# Connectors.net
KiCad netlist of a schematic drawn in Altium Designer
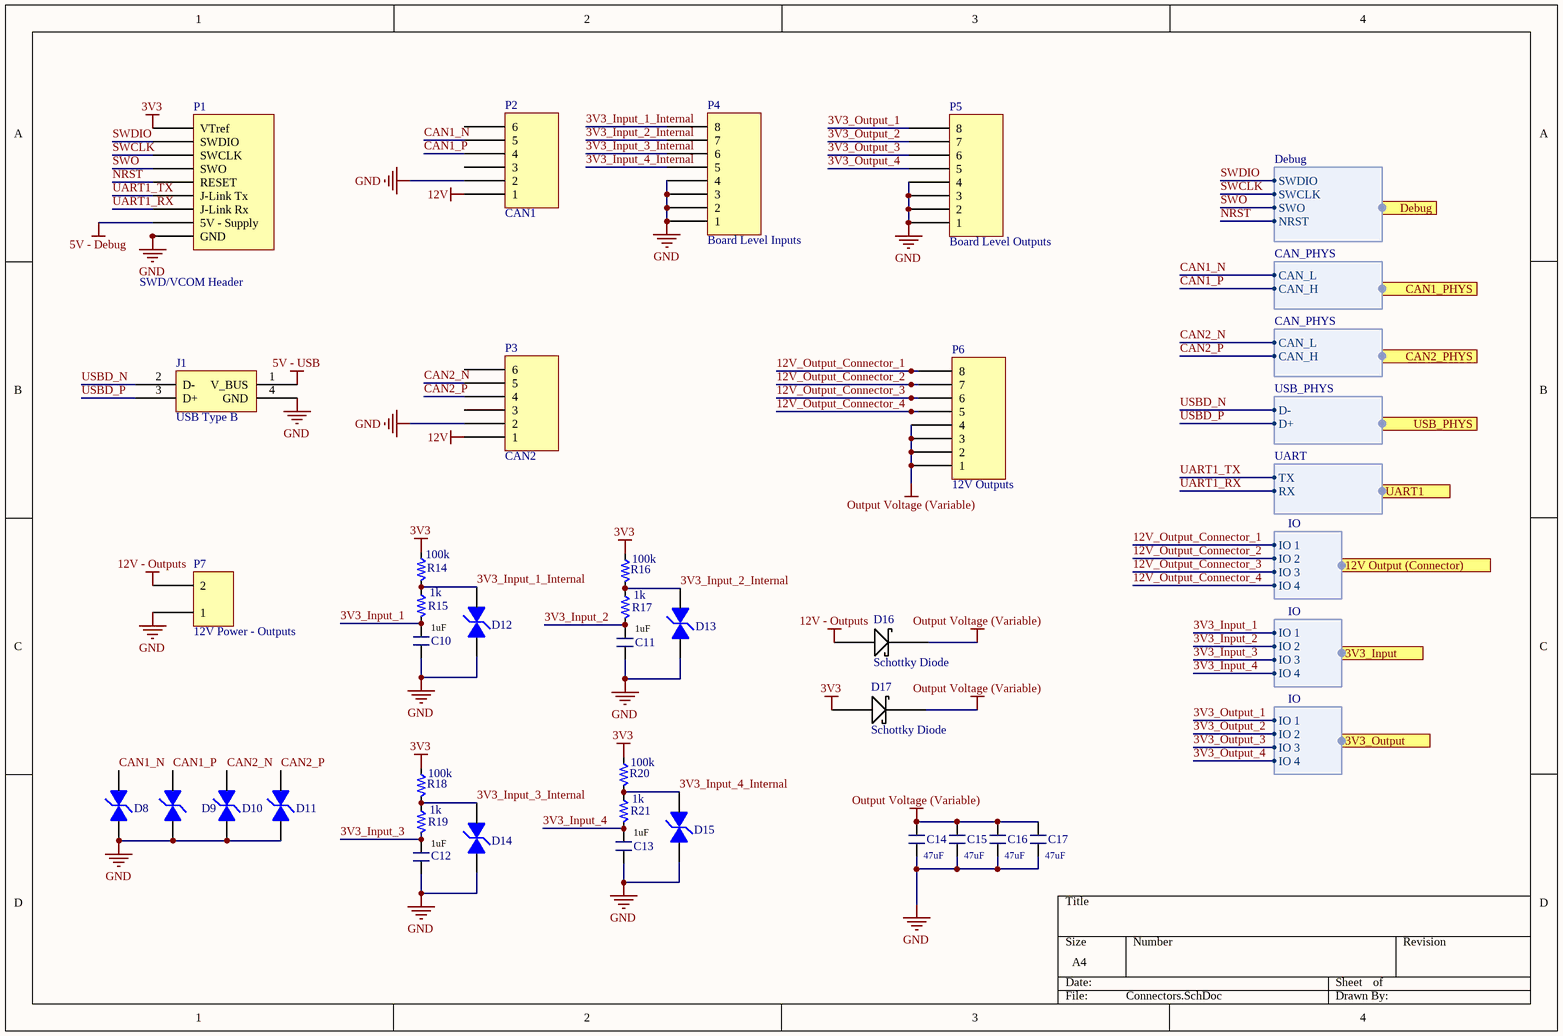
[diagram p0: Connectors.SchDoc]

(export (version "E")
  (design (tool "Eeschema 10.0.6"))
  (components
    (comp (ref "C10")
      (value "SCH_GENERIC_CAPACITOR_0603")
      (footprint "PCB_GENERIC_SMD_0603")
      (description "Generic SMD capacitor 0603")
      (fields (field (name "TOLERANCE") "*%") (field (name "CAPACITANCE") "1uF"))
      (libsource (lib "Generic 0603 Capacitor") (part "SCH_GENERIC_CAPACITOR_0603"))
    )
    (comp (ref "C11")
      (value "SCH_GENERIC_CAPACITOR_0603")
      (footprint "PCB_GENERIC_SMD_0603")
      (description "Generic SMD capacitor 0603")
      (fields (field (name "TOLERANCE") "*%") (field (name "CAPACITANCE") "1uF"))
      (libsource (lib "Generic 0603 Capacitor") (part "SCH_GENERIC_CAPACITOR_0603"))
    )
    (comp (ref "C12")
      (value "SCH_GENERIC_CAPACITOR_0603")
      (footprint "PCB_GENERIC_SMD_0603")
      (description "Generic SMD capacitor 0603")
      (fields (field (name "TOLERANCE") "*%") (field (name "CAPACITANCE") "1uF"))
      (libsource (lib "Generic 0603 Capacitor") (part "SCH_GENERIC_CAPACITOR_0603"))
    )
    (comp (ref "C13")
      (value "SCH_GENERIC_CAPACITOR_0603")
      (footprint "PCB_GENERIC_SMD_0603")
      (description "Generic SMD capacitor 0603")
      (fields (field (name "TOLERANCE") "*%") (field (name "CAPACITANCE") "1uF"))
      (libsource (lib "Generic 0603 Capacitor") (part "SCH_GENERIC_CAPACITOR_0603"))
    )
    (comp (ref "C14")
      (value "SCH_GENERIC_CAPACITOR_1210")
      (footprint "PCB_GENERIC_CAPACITOR_1210")
      (description "Generic SMD capacitor 1210")
      (fields (field (name "CAPACITANCE") "47uF"))
      (libsource (lib "Generic 1210 Capacitor") (part "SCH_GENERIC_CAPACITOR_1210"))
    )
    (comp (ref "C15")
      (value "SCH_GENERIC_CAPACITOR_1210")
      (footprint "PCB_GENERIC_CAPACITOR_1210")
      (description "Generic SMD capacitor 1210")
      (fields (field (name "CAPACITANCE") "47uF"))
      (libsource (lib "Generic 1210 Capacitor") (part "SCH_GENERIC_CAPACITOR_1210"))
    )
    (comp (ref "C16")
      (value "SCH_GENERIC_CAPACITOR_1210")
      (footprint "PCB_GENERIC_CAPACITOR_1210")
      (description "Generic SMD capacitor 1210")
      (fields (field (name "CAPACITANCE") "47uF"))
      (libsource (lib "Generic 1210 Capacitor") (part "SCH_GENERIC_CAPACITOR_1210"))
    )
    (comp (ref "C17")
      (value "SCH_GENERIC_CAPACITOR_1210")
      (footprint "PCB_GENERIC_CAPACITOR_1210")
      (description "Generic SMD capacitor 1210")
      (fields (field (name "CAPACITANCE") "47uF"))
      (libsource (lib "Generic 1210 Capacitor") (part "SCH_GENERIC_CAPACITOR_1210"))
    )
    (comp (ref "D8")
      (value "TVS Diode")
      (footprint "TVS Diode")
      (fields (field (name "MANUFACTURER") "Bourns"))
      (libsource (lib "TVS Diode") (part "TVS Diode"))
    )
    (comp (ref "D9")
      (value "TVS Diode")
      (footprint "TVS Diode")
      (fields (field (name "MANUFACTURER") "Bourns"))
      (libsource (lib "TVS Diode") (part "TVS Diode"))
    )
    (comp (ref "D10")
      (value "TVS Diode")
      (footprint "TVS Diode")
      (fields (field (name "MANUFACTURER") "Bourns"))
      (libsource (lib "TVS Diode") (part "TVS Diode"))
    )
    (comp (ref "D11")
      (value "TVS Diode")
      (footprint "TVS Diode")
      (fields (field (name "MANUFACTURER") "Bourns"))
      (libsource (lib "TVS Diode") (part "TVS Diode"))
    )
    (comp (ref "D12")
      (value "TVS Diode")
      (footprint "TVS Diode")
      (fields (field (name "MANUFACTURER") "Bourns"))
      (libsource (lib "TVS Diode") (part "TVS Diode"))
    )
    (comp (ref "D13")
      (value "TVS Diode")
      (footprint "TVS Diode")
      (fields (field (name "MANUFACTURER") "Bourns"))
      (libsource (lib "TVS Diode") (part "TVS Diode"))
    )
    (comp (ref "D14")
      (value "TVS Diode")
      (footprint "TVS Diode")
      (fields (field (name "MANUFACTURER") "Bourns"))
      (libsource (lib "TVS Diode") (part "TVS Diode"))
    )
    (comp (ref "D15")
      (value "TVS Diode")
      (footprint "TVS Diode")
      (fields (field (name "MANUFACTURER") "Bourns"))
      (libsource (lib "TVS Diode") (part "TVS Diode"))
    )
    (comp (ref "D16")
      (value "Schottky Diode")
      (footprint "ON Semi Schottky Diode - MBRM110LT1G")
      (libsource (lib "ON Semi Schottky Diode") (part "ON Semi Schottky Diode - MBRM110LT1G"))
    )
    (comp (ref "D17")
      (value "Schottky Diode")
      (footprint "ON Semi Schottky Diode - MBRM110LT1G")
      (libsource (lib "ON Semi Schottky Diode") (part "ON Semi Schottky Diode - MBRM110LT1G"))
    )
    (comp (ref "J1")
      (value "USB Type B")
      (footprint "0670688000")
      (libsource (lib "USB Type B Right Angle") (part "0670688000"))
    )
    (comp (ref "P1")
      (value "SWD/VCOM Header")
      (footprint "Samtec TST-110-01-G-D")
      (libsource (lib "SWD+VCOM Header - J-Link") (part "SWD/VCOM Header"))
    )
    (comp (ref "P2")
      (value "CAN1")
      (footprint "Molex Microfit 3.0 3x2:PCB_MLX_MICROFIT_3X2")
      (libsource (lib "Molex Microfit 3.0 3x2") (part "SCH_MLX_MICROFIT_3X2"))
    )
    (comp (ref "P3")
      (value "CAN2")
      (footprint "Molex Microfit 3.0 3x2:PCB_MLX_MICROFIT_3X2")
      (libsource (lib "Molex Microfit 3.0 3x2") (part "SCH_MLX_MICROFIT_3X2"))
    )
    (comp (ref "P4")
      (value "Board Level Inputs")
      (footprint "Molex Microfit 3.0 4x2:PCB_MLX_MICROFIT_4X2")
      (description "Molex Microfit Connector 4x2")
      (libsource (lib "Molex Microfit 3.0 4x2") (part "SCH_MLX_MICROFIT_4X2"))
    )
    (comp (ref "P5")
      (value "Board Level Outputs")
      (footprint "Molex Microfit 3.0 4x2:PCB_MLX_MICROFIT_4X2")
      (description "Molex Microfit Connector 4x2")
      (libsource (lib "Molex Microfit 3.0 4x2") (part "SCH_MLX_MICROFIT_4X2"))
    )
    (comp (ref "P6")
      (value "12V Outputs")
      (footprint "Molex Microfit 3.0 4x2:PCB_MLX_MICROFIT_4X2")
      (description "Molex Microfit Connector 4x2")
      (libsource (lib "Molex Microfit 3.0 4x2") (part "SCH_MLX_MICROFIT_4X2"))
    )
    (comp (ref "P7")
      (value "12V Power - Outputs")
      (footprint "Molex Mini-Fit Jr 2x1")
      (libsource (lib "Molex Mini-Fit Jr 1x2") (part "Molex Mini-Fit 1x2"))
    )
    (comp (ref "R14")
      (value "SCH_GENERIC_RESISTOR_0603")
      (footprint "PCB_GENERIC_SMD_0603")
      (description "Generic SMD resistor 0603")
      (fields (field (name "RESISTANCE") "100k"))
      (libsource (lib "Generic 0603 Resistor") (part "SCH_GENERIC_RESISTOR_0603"))
    )
    (comp (ref "R15")
      (value "SCH_GENERIC_RESISTOR_0603")
      (footprint "PCB_GENERIC_SMD_0603")
      (description "Generic SMD resistor 0603")
      (fields (field (name "RESISTANCE") "1k"))
      (libsource (lib "Generic 0603 Resistor") (part "SCH_GENERIC_RESISTOR_0603"))
    )
    (comp (ref "R16")
      (value "SCH_GENERIC_RESISTOR_0603")
      (footprint "PCB_GENERIC_SMD_0603")
      (description "Generic SMD resistor 0603")
      (fields (field (name "RESISTANCE") "100k"))
      (libsource (lib "Generic 0603 Resistor") (part "SCH_GENERIC_RESISTOR_0603"))
    )
    (comp (ref "R17")
      (value "SCH_GENERIC_RESISTOR_0603")
      (footprint "PCB_GENERIC_SMD_0603")
      (description "Generic SMD resistor 0603")
      (fields (field (name "RESISTANCE") "1k"))
      (libsource (lib "Generic 0603 Resistor") (part "SCH_GENERIC_RESISTOR_0603"))
    )
    (comp (ref "R18")
      (value "SCH_GENERIC_RESISTOR_0603")
      (footprint "PCB_GENERIC_SMD_0603")
      (description "Generic SMD resistor 0603")
      (fields (field (name "RESISTANCE") "100k"))
      (libsource (lib "Generic 0603 Resistor") (part "SCH_GENERIC_RESISTOR_0603"))
    )
    (comp (ref "R19")
      (value "SCH_GENERIC_RESISTOR_0603")
      (footprint "PCB_GENERIC_SMD_0603")
      (description "Generic SMD resistor 0603")
      (fields (field (name "RESISTANCE") "1k"))
      (libsource (lib "Generic 0603 Resistor") (part "SCH_GENERIC_RESISTOR_0603"))
    )
    (comp (ref "R20")
      (value "SCH_GENERIC_RESISTOR_0603")
      (footprint "PCB_GENERIC_SMD_0603")
      (description "Generic SMD resistor 0603")
      (fields (field (name "RESISTANCE") "100k"))
      (libsource (lib "Generic 0603 Resistor") (part "SCH_GENERIC_RESISTOR_0603"))
    )
    (comp (ref "R21")
      (value "SCH_GENERIC_RESISTOR_0603")
      (footprint "PCB_GENERIC_SMD_0603")
      (description "Generic SMD resistor 0603")
      (fields (field (name "RESISTANCE") "1k"))
      (libsource (lib "Generic 0603 Resistor") (part "SCH_GENERIC_RESISTOR_0603"))
    )
  )
  (nets
    (net (code "6") (name "/3V3_Input_1") (class "Default")
      (node (ref "C10") (pin "2") (pinfunction "2_2") (pintype "passive"))
      (node (ref "R15") (pin "2") (pinfunction "2_2") (pintype "passive"))
    )
    (net (code "7") (name "/3V3_Input_1_Internal") (class "Default")
      (node (ref "D12") (pin "1") (pintype "passive"))
      (node (ref "P4") (pin "8") (pinfunction "8_8") (pintype "passive"))
      (node (ref "R14") (pin "2") (pinfunction "2_2") (pintype "passive"))
      (node (ref "R15") (pin "1") (pinfunction "1_1") (pintype "passive"))
    )
    (net (code "8") (name "/3V3_Input_2") (class "Default")
      (node (ref "C11") (pin "2") (pinfunction "2_2") (pintype "passive"))
      (node (ref "R17") (pin "2") (pinfunction "2_2") (pintype "passive"))
    )
    (net (code "9") (name "/3V3_Input_2_Internal") (class "Default")
      (node (ref "D13") (pin "1") (pintype "passive"))
      (node (ref "P4") (pin "7") (pinfunction "7_7") (pintype "passive"))
      (node (ref "R16") (pin "2") (pinfunction "2_2") (pintype "passive"))
      (node (ref "R17") (pin "1") (pinfunction "1_1") (pintype "passive"))
    )
    (net (code "10") (name "/3V3_Input_3") (class "Default")
      (node (ref "C12") (pin "2") (pinfunction "2_2") (pintype "passive"))
      (node (ref "R19") (pin "2") (pinfunction "2_2") (pintype "passive"))
    )
    (net (code "11") (name "/3V3_Input_3_Internal") (class "Default")
      (node (ref "D14") (pin "1") (pintype "passive"))
      (node (ref "P4") (pin "6") (pinfunction "6_6") (pintype "passive"))
      (node (ref "R18") (pin "2") (pinfunction "2_2") (pintype "passive"))
      (node (ref "R19") (pin "1") (pinfunction "1_1") (pintype "passive"))
    )
    (net (code "12") (name "/3V3_Input_4") (class "Default")
      (node (ref "C13") (pin "2") (pinfunction "2_2") (pintype "passive"))
      (node (ref "R21") (pin "2") (pinfunction "2_2") (pintype "passive"))
    )
    (net (code "13") (name "/3V3_Input_4_Internal") (class "Default")
      (node (ref "D15") (pin "1") (pintype "passive"))
      (node (ref "P4") (pin "5") (pinfunction "5_5") (pintype "passive"))
      (node (ref "R20") (pin "2") (pinfunction "2_2") (pintype "passive"))
      (node (ref "R21") (pin "1") (pinfunction "1_1") (pintype "passive"))
    )
    (net (code "14") (name "/3V3_Output_1") (class "Default")
      (node (ref "P5") (pin "8") (pinfunction "8_8") (pintype "passive"))
    )
    (net (code "15") (name "/3V3_Output_2") (class "Default")
      (node (ref "P5") (pin "7") (pinfunction "7_7") (pintype "passive"))
    )
    (net (code "16") (name "/3V3_Output_3") (class "Default")
      (node (ref "P5") (pin "6") (pinfunction "6_6") (pintype "passive"))
    )
    (net (code "17") (name "/3V3_Output_4") (class "Default")
      (node (ref "P5") (pin "5") (pinfunction "5_5") (pintype "passive"))
    )
    (net (code "18") (name "/12V_Output_Connector_1") (class "Default")
      (node (ref "P6") (pin "8") (pinfunction "8_8") (pintype "passive"))
    )
    (net (code "19") (name "/12V_Output_Connector_2") (class "Default")
      (node (ref "P6") (pin "7") (pinfunction "7_7") (pintype "passive"))
    )
    (net (code "20") (name "/12V_Output_Connector_3") (class "Default")
      (node (ref "P6") (pin "6") (pinfunction "6_6") (pintype "passive"))
    )
    (net (code "21") (name "/12V_Output_Connector_4") (class "Default")
      (node (ref "P6") (pin "5") (pinfunction "5_5") (pintype "passive"))
    )
    (net (code "22") (name "/CAN1_N") (class "Default")
      (node (ref "D8") (pin "1") (pintype "passive"))
      (node (ref "P2") (pin "5") (pinfunction "5_5") (pintype "passive"))
    )
    (net (code "23") (name "/CAN1_P") (class "Default")
      (node (ref "D9") (pin "1") (pintype "passive"))
      (node (ref "P2") (pin "4") (pinfunction "4_4") (pintype "passive"))
    )
    (net (code "24") (name "/CAN2_N") (class "Default")
      (node (ref "D10") (pin "1") (pintype "passive"))
      (node (ref "P3") (pin "5") (pinfunction "5_5") (pintype "passive"))
    )
    (net (code "25") (name "/CAN2_P") (class "Default")
      (node (ref "D11") (pin "1") (pintype "passive"))
      (node (ref "P3") (pin "4") (pinfunction "4_4") (pintype "passive"))
    )
    (net (code "26") (name "/NRST") (class "Default")
      (node (ref "P1") (pin "15") (pinfunction "RESET_15") (pintype "passive"))
    )
    (net (code "27") (name "/SWCLK") (class "Default")
      (node (ref "P1") (pin "9") (pinfunction "SWCLK_9") (pintype "passive"))
    )
    (net (code "28") (name "/SWDIO") (class "Default")
      (node (ref "P1") (pin "7") (pinfunction "SWDIO_7") (pintype "passive"))
    )
    (net (code "29") (name "/SWO") (class "Default")
      (node (ref "P1") (pin "13") (pinfunction "SWO_13") (pintype "passive"))
    )
    (net (code "30") (name "/UART1_RX") (class "Default")
      (node (ref "P1") (pin "17") (pinfunction "J-Link_Rx_17") (pintype "passive"))
    )
    (net (code "31") (name "/UART1_TX") (class "Default")
      (node (ref "P1") (pin "5") (pinfunction "J-Link_Tx_5") (pintype "passive"))
    )
    (net (code "32") (name "/USBD_N") (class "Default")
      (node (ref "J1") (pin "2") (pinfunction "D-_2") (pintype "passive"))
    )
    (net (code "33") (name "/USBD_P") (class "Default")
      (node (ref "J1") (pin "3") (pinfunction "D+_3") (pintype "passive"))
    )
    (net (code "39") (name "3V3") (class "Default")
      (node (ref "D17") (pin "2") (pinfunction "2_2") (pintype "passive"))
      (node (ref "P1") (pin "1") (pinfunction "VTref_1") (pintype "passive"))
      (node (ref "R14") (pin "1") (pinfunction "1_1") (pintype "passive"))
      (node (ref "R16") (pin "1") (pinfunction "1_1") (pintype "passive"))
      (node (ref "R18") (pin "1") (pinfunction "1_1") (pintype "passive"))
      (node (ref "R20") (pin "1") (pinfunction "1_1") (pintype "passive"))
    )
    (net (code "40") (name "5V - Debug") (class "Default")
      (node (ref "P1") (pin "19") (pinfunction "5V_-_Supply_19") (pintype "passive"))
    )
    (net (code "41") (name "5V - USB") (class "Default")
      (node (ref "J1") (pin "1") (pinfunction "V_BUS_1") (pintype "passive"))
    )
    (net (code "42") (name "12V") (class "Default")
      (node (ref "P2") (pin "1") (pinfunction "1_1") (pintype "passive"))
      (node (ref "P3") (pin "1") (pinfunction "1_1") (pintype "passive"))
    )
    (net (code "43") (name "12V - Outputs") (class "Default")
      (node (ref "D16") (pin "2") (pinfunction "2_2") (pintype "passive"))
      (node (ref "P7") (pin "2") (pinfunction "2_2") (pintype "passive"))
    )
    (net (code "44") (name "GND") (class "Default")
      (node (ref "C10") (pin "1") (pinfunction "1_1") (pintype "passive"))
      (node (ref "C11") (pin "1") (pinfunction "1_1") (pintype "passive"))
      (node (ref "C12") (pin "1") (pinfunction "1_1") (pintype "passive"))
      (node (ref "C13") (pin "1") (pinfunction "1_1") (pintype "passive"))
      (node (ref "C14") (pin "1") (pinfunction "1_1") (pintype "passive"))
      (node (ref "C15") (pin "1") (pinfunction "1_1") (pintype "passive"))
      (node (ref "C16") (pin "1") (pinfunction "1_1") (pintype "passive"))
      (node (ref "C17") (pin "1") (pinfunction "1_1") (pintype "passive"))
      (node (ref "D10") (pin "2") (pintype "passive"))
      (node (ref "D11") (pin "2") (pintype "passive"))
      (node (ref "D12") (pin "2") (pintype "passive"))
      (node (ref "D13") (pin "2") (pintype "passive"))
      (node (ref "D14") (pin "2") (pintype "passive"))
      (node (ref "D15") (pin "2") (pintype "passive"))
      (node (ref "D8") (pin "2") (pintype "passive"))
      (node (ref "D9") (pin "2") (pintype "passive"))
      (node (ref "J1") (pin "4") (pinfunction "GND_4") (pintype "passive"))
      (node (ref "P1") (pin "10") (pinfunction "GND_10") (pintype "passive"))
      (node (ref "P1") (pin "12") (pinfunction "GND_12") (pintype "passive"))
      (node (ref "P1") (pin "4") (pinfunction "GND_4") (pintype "passive"))
      (node (ref "P1") (pin "6") (pinfunction "GND_6") (pintype "passive"))
      (node (ref "P1") (pin "8") (pinfunction "GND_8") (pintype "passive"))
      (node (ref "P2") (pin "2") (pinfunction "2_2") (pintype "passive"))
      (node (ref "P3") (pin "2") (pinfunction "2_2") (pintype "passive"))
      (node (ref "P4") (pin "1") (pinfunction "1_1") (pintype "passive"))
      (node (ref "P4") (pin "2") (pinfunction "2_2") (pintype "passive"))
      (node (ref "P4") (pin "3") (pinfunction "3_3") (pintype "passive"))
      (node (ref "P4") (pin "4") (pinfunction "4_4") (pintype "passive"))
      (node (ref "P5") (pin "1") (pinfunction "1_1") (pintype "passive"))
      (node (ref "P5") (pin "2") (pinfunction "2_2") (pintype "passive"))
      (node (ref "P5") (pin "3") (pinfunction "3_3") (pintype "passive"))
      (node (ref "P5") (pin "4") (pinfunction "4_4") (pintype "passive"))
      (node (ref "P7") (pin "1") (pinfunction "1_1") (pintype "passive"))
    )
    (net (code "45") (name "Output Voltage (Variable)") (class "Default")
      (node (ref "C14") (pin "2") (pinfunction "2_2") (pintype "passive"))
      (node (ref "C15") (pin "2") (pinfunction "2_2") (pintype "passive"))
      (node (ref "C16") (pin "2") (pinfunction "2_2") (pintype "passive"))
      (node (ref "C17") (pin "2") (pinfunction "2_2") (pintype "passive"))
      (node (ref "D16") (pin "1") (pinfunction "1_1") (pintype "passive"))
      (node (ref "D17") (pin "1") (pinfunction "1_1") (pintype "passive"))
      (node (ref "P6") (pin "1") (pinfunction "1_1") (pintype "passive"))
      (node (ref "P6") (pin "2") (pinfunction "2_2") (pintype "passive"))
      (node (ref "P6") (pin "3") (pinfunction "3_3") (pintype "passive"))
      (node (ref "P6") (pin "4") (pinfunction "4_4") (pintype "passive"))
    )
    (net (code "46") (name "unconnected-(P2-Pad3)") (class "Default")
      (node (ref "P2") (pin "3") (pinfunction "3_3") (pintype "passive"))
    )
    (net (code "47") (name "unconnected-(P2-Pad6)") (class "Default")
      (node (ref "P2") (pin "6") (pinfunction "6_6") (pintype "passive"))
    )
    (net (code "48") (name "unconnected-(P3-Pad3)") (class "Default")
      (node (ref "P3") (pin "3") (pinfunction "3_3") (pintype "passive"))
    )
    (net (code "49") (name "unconnected-(P3-Pad6)") (class "Default")
      (node (ref "P3") (pin "6") (pinfunction "6_6") (pintype "passive"))
    )
  )
)
